# OutputConnectors.net
KiCad netlist of a schematic drawn in Altium Designer
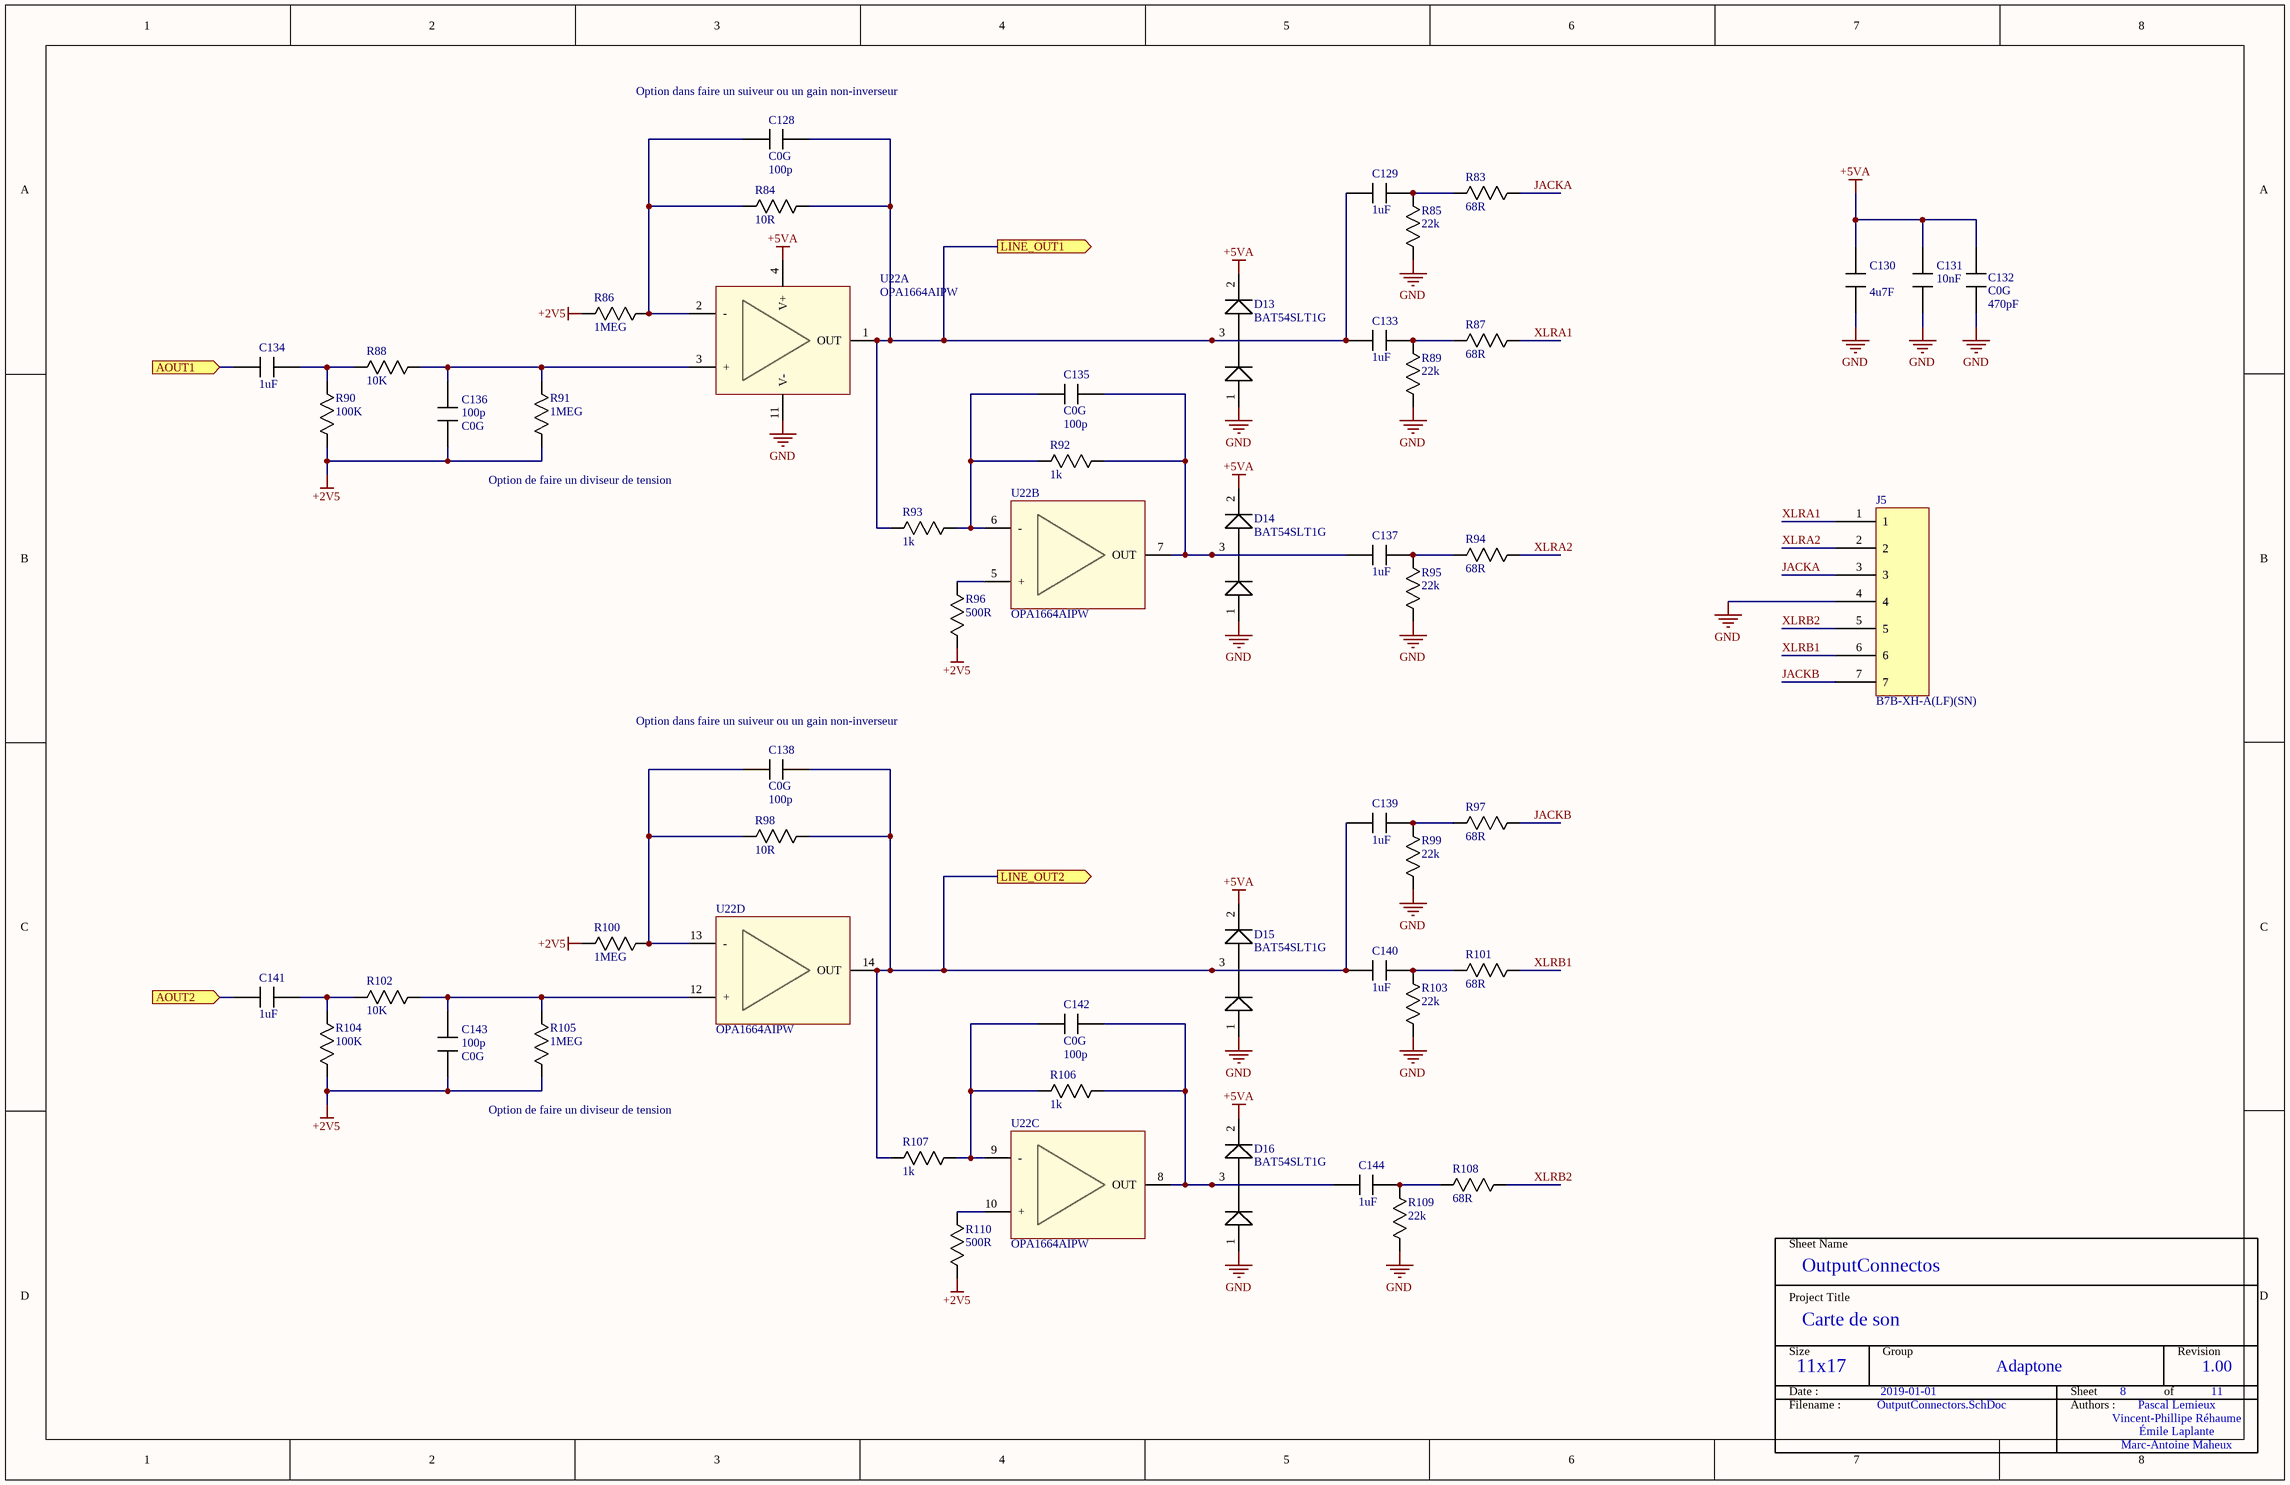
[diagram p0: OutputConnectors.SchDoc]

(export (version "E")
  (design (tool "Eeschema 10.0.6"))
  (components
    (comp (ref "C128")
      (value "100p")
      (footprint "0402")
      (description "Capacitor")
      (fields (field (name "MFG") "Yageo") (field (name "TYPE") "C0G"))
      (libsource (lib "LIB_ADAPTONE_PASCAL_LEMIEUX") (part "Capacitor"))
    )
    (comp (ref "C129")
      (value "1uF")
      (footprint "0402")
      (description "Capacitor")
      (fields (field (name "MFG") "Samsung Electro-Mechanics"))
      (libsource (lib "LIB_ADAPTONE_PASCAL_LEMIEUX") (part "Capacitor"))
    )
    (comp (ref "C130")
      (value "4u7F")
      (footprint "0805")
      (description "Capacitor")
      (fields (field (name "MFG") "Samsung"))
      (libsource (lib "ADAPTONE_CARTE_DE_SON") (part "Capacitor"))
    )
    (comp (ref "C131")
      (value "10nF")
      (footprint "0603")
      (description "Capacitor")
      (fields (field (name "MFG") "Murata"))
      (libsource (lib "ADAPTONE_CARTE_DE_SON") (part "Capacitor"))
    )
    (comp (ref "C132")
      (value "470pF")
      (footprint "0603")
      (description "Capacitor")
      (fields (field (name "MFG") "Samsung") (field (name "TYPE") "C0G"))
      (libsource (lib "ADAPTONE_CARTE_DE_SON") (part "Capacitor"))
    )
    (comp (ref "C133")
      (value "1uF")
      (footprint "0402")
      (description "Capacitor")
      (fields (field (name "MFG") "Samsung Electro-Mechanics"))
      (libsource (lib "LIB_ADAPTONE_PASCAL_LEMIEUX") (part "Capacitor"))
    )
    (comp (ref "C134")
      (value "1uF")
      (footprint "0402")
      (description "Capacitor")
      (fields (field (name "MFG") "Samsung Electro-Mechanics"))
      (libsource (lib "LIB_ADAPTONE_PASCAL_LEMIEUX") (part "Capacitor"))
    )
    (comp (ref "C135")
      (value "100p")
      (footprint "0402")
      (description "Capacitor")
      (fields (field (name "MFG") "Yageo") (field (name "TYPE") "C0G"))
      (libsource (lib "LIB_ADAPTONE_PASCAL_LEMIEUX") (part "Capacitor"))
    )
    (comp (ref "C136")
      (value "100p")
      (footprint "0402")
      (description "Capacitor")
      (fields (field (name "MFG") "Yageo") (field (name "TYPE") "C0G"))
      (libsource (lib "LIB_ADAPTONE_PASCAL_LEMIEUX") (part "Capacitor"))
    )
    (comp (ref "C137")
      (value "1uF")
      (footprint "0402")
      (description "Capacitor")
      (fields (field (name "MFG") "Samsung Electro-Mechanics"))
      (libsource (lib "LIB_ADAPTONE_PASCAL_LEMIEUX") (part "Capacitor"))
    )
    (comp (ref "C138")
      (value "100p")
      (footprint "0402")
      (description "Capacitor")
      (fields (field (name "MFG") "Yageo") (field (name "TYPE") "C0G"))
      (libsource (lib "LIB_ADAPTONE_PASCAL_LEMIEUX") (part "Capacitor"))
    )
    (comp (ref "C139")
      (value "1uF")
      (footprint "0402")
      (description "Capacitor")
      (fields (field (name "MFG") "Samsung Electro-Mechanics"))
      (libsource (lib "LIB_ADAPTONE_PASCAL_LEMIEUX") (part "Capacitor"))
    )
    (comp (ref "C140")
      (value "1uF")
      (footprint "0402")
      (description "Capacitor")
      (fields (field (name "MFG") "Samsung Electro-Mechanics"))
      (libsource (lib "LIB_ADAPTONE_PASCAL_LEMIEUX") (part "Capacitor"))
    )
    (comp (ref "C141")
      (value "1uF")
      (footprint "0402")
      (description "Capacitor")
      (fields (field (name "MFG") "Samsung Electro-Mechanics"))
      (libsource (lib "LIB_ADAPTONE_PASCAL_LEMIEUX") (part "Capacitor"))
    )
    (comp (ref "C142")
      (value "100p")
      (footprint "0402")
      (description "Capacitor")
      (fields (field (name "MFG") "Yageo") (field (name "TYPE") "C0G"))
      (libsource (lib "LIB_ADAPTONE_PASCAL_LEMIEUX") (part "Capacitor"))
    )
    (comp (ref "C143")
      (value "100p")
      (footprint "0402")
      (description "Capacitor")
      (fields (field (name "MFG") "Yageo") (field (name "TYPE") "C0G"))
      (libsource (lib "LIB_ADAPTONE_PASCAL_LEMIEUX") (part "Capacitor"))
    )
    (comp (ref "C144")
      (value "1uF")
      (footprint "0402")
      (description "Capacitor")
      (fields (field (name "MFG") "Samsung Electro-Mechanics"))
      (libsource (lib "LIB_ADAPTONE_PASCAL_LEMIEUX") (part "Capacitor"))
    )
    (comp (ref "D13")
      (value "Diode_dual")
      (footprint "SOT23_132")
      (description "Diode")
      (fields (field (name "MFG") "Onsemi") (field (name "MFG_PN") "BAT54SLT1G"))
      (libsource (lib "ADAPTONE_CARTE_DE_SON") (part "Diode_dual"))
    )
    (comp (ref "D14")
      (value "Diode_dual")
      (footprint "SOT23_132")
      (description "Diode")
      (fields (field (name "MFG") "Onsemi") (field (name "MFG_PN") "BAT54SLT1G"))
      (libsource (lib "ADAPTONE_CARTE_DE_SON") (part "Diode_dual"))
    )
    (comp (ref "D15")
      (value "Diode_dual")
      (footprint "SOT23_132")
      (description "Diode")
      (fields (field (name "MFG") "Onsemi") (field (name "MFG_PN") "BAT54SLT1G"))
      (libsource (lib "ADAPTONE_CARTE_DE_SON") (part "Diode_dual"))
    )
    (comp (ref "D16")
      (value "Diode_dual")
      (footprint "SOT23_132")
      (description "Diode")
      (fields (field (name "MFG") "Onsemi") (field (name "MFG_PN") "BAT54SLT1G"))
      (libsource (lib "ADAPTONE_CARTE_DE_SON") (part "Diode_dual"))
    )
    (comp (ref "J5")
      (value "B7B-XH-A(LF)(SN)")
      (footprint "CONN_7_HEADER")
      (fields (field (name "MFG") "JST Sales America Inc."))
      (libsource (lib "LIB_ADAPTONE_PASCAL_LEMIEUX") (part "CON_XH_JST_7pins"))
    )
    (comp (ref "R83")
      (value "68R")
      (footprint "0402")
      (description "Resistor")
      (fields (field (name "MFG") "Yageo"))
      (libsource (lib "LIB_ADAPTONE_PASCAL_LEMIEUX") (part "Resistor"))
    )
    (comp (ref "R84")
      (value "10R")
      (footprint "0402")
      (description "Resistor")
      (fields (field (name "MFG") "Yageo"))
      (libsource (lib "LIB_ADAPTONE_PASCAL_LEMIEUX") (part "Resistor"))
    )
    (comp (ref "R85")
      (value "22k")
      (footprint "0402")
      (description "Resistor")
      (fields (field (name "MFG") "Yageo"))
      (libsource (lib "LIB_ADAPTONE_PASCAL_LEMIEUX") (part "Resistor"))
    )
    (comp (ref "R86")
      (value "1MEG")
      (footprint "0402")
      (description "Resistor")
      (fields (field (name "MFG") "Yageo"))
      (libsource (lib "LIB_ADAPTONE_PASCAL_LEMIEUX") (part "Resistor"))
    )
    (comp (ref "R87")
      (value "68R")
      (footprint "0402")
      (description "Resistor")
      (fields (field (name "MFG") "Yageo"))
      (libsource (lib "LIB_ADAPTONE_PASCAL_LEMIEUX") (part "Resistor"))
    )
    (comp (ref "R88")
      (value "10K")
      (footprint "0402")
      (description "Resistor")
      (fields (field (name "MFG") "Yageo"))
      (libsource (lib "LIB_ADAPTONE_PASCAL_LEMIEUX") (part "Resistor"))
    )
    (comp (ref "R89")
      (value "22k")
      (footprint "0402")
      (description "Resistor")
      (fields (field (name "MFG") "Yageo"))
      (libsource (lib "LIB_ADAPTONE_PASCAL_LEMIEUX") (part "Resistor"))
    )
    (comp (ref "R90")
      (value "100K")
      (footprint "0402")
      (description "Resistor")
      (fields (field (name "MFG") "Yageo"))
      (libsource (lib "LIB_ADAPTONE_PASCAL_LEMIEUX") (part "Resistor"))
    )
    (comp (ref "R91")
      (value "1MEG")
      (footprint "0402")
      (description "Resistor")
      (fields (field (name "MFG") "Yageo"))
      (libsource (lib "LIB_ADAPTONE_PASCAL_LEMIEUX") (part "Resistor"))
    )
    (comp (ref "R92")
      (value "1k")
      (footprint "0402")
      (description "Resistor")
      (fields (field (name "MFG") "Yageo"))
      (libsource (lib "LIB_ADAPTONE_PASCAL_LEMIEUX") (part "Resistor"))
    )
    (comp (ref "R93")
      (value "1k")
      (footprint "0402")
      (description "Resistor")
      (fields (field (name "MFG") "Yageo"))
      (libsource (lib "LIB_ADAPTONE_PASCAL_LEMIEUX") (part "Resistor"))
    )
    (comp (ref "R94")
      (value "68R")
      (footprint "0402")
      (description "Resistor")
      (fields (field (name "MFG") "Yageo"))
      (libsource (lib "LIB_ADAPTONE_PASCAL_LEMIEUX") (part "Resistor"))
    )
    (comp (ref "R95")
      (value "22k")
      (footprint "0402")
      (description "Resistor")
      (fields (field (name "MFG") "Yageo"))
      (libsource (lib "LIB_ADAPTONE_PASCAL_LEMIEUX") (part "Resistor"))
    )
    (comp (ref "R96")
      (value "500R")
      (footprint "0402")
      (description "Resistor")
      (fields (field (name "MFG") "Yageo"))
      (libsource (lib "LIB_ADAPTONE_PASCAL_LEMIEUX") (part "Resistor"))
    )
    (comp (ref "R97")
      (value "68R")
      (footprint "0402")
      (description "Resistor")
      (fields (field (name "MFG") "Yageo"))
      (libsource (lib "LIB_ADAPTONE_PASCAL_LEMIEUX") (part "Resistor"))
    )
    (comp (ref "R98")
      (value "10R")
      (footprint "0402")
      (description "Resistor")
      (fields (field (name "MFG") "Yageo"))
      (libsource (lib "LIB_ADAPTONE_PASCAL_LEMIEUX") (part "Resistor"))
    )
    (comp (ref "R99")
      (value "22k")
      (footprint "0402")
      (description "Resistor")
      (fields (field (name "MFG") "Yageo"))
      (libsource (lib "LIB_ADAPTONE_PASCAL_LEMIEUX") (part "Resistor"))
    )
    (comp (ref "R100")
      (value "1MEG")
      (footprint "0402")
      (description "Resistor")
      (fields (field (name "MFG") "Yageo"))
      (libsource (lib "LIB_ADAPTONE_PASCAL_LEMIEUX") (part "Resistor"))
    )
    (comp (ref "R101")
      (value "68R")
      (footprint "0402")
      (description "Resistor")
      (fields (field (name "MFG") "Yageo"))
      (libsource (lib "LIB_ADAPTONE_PASCAL_LEMIEUX") (part "Resistor"))
    )
    (comp (ref "R102")
      (value "10K")
      (footprint "0402")
      (description "Resistor")
      (fields (field (name "MFG") "Yageo"))
      (libsource (lib "LIB_ADAPTONE_PASCAL_LEMIEUX") (part "Resistor"))
    )
    (comp (ref "R103")
      (value "22k")
      (footprint "0402")
      (description "Resistor")
      (fields (field (name "MFG") "Yageo"))
      (libsource (lib "LIB_ADAPTONE_PASCAL_LEMIEUX") (part "Resistor"))
    )
    (comp (ref "R104")
      (value "100K")
      (footprint "0402")
      (description "Resistor")
      (fields (field (name "MFG") "Yageo"))
      (libsource (lib "LIB_ADAPTONE_PASCAL_LEMIEUX") (part "Resistor"))
    )
    (comp (ref "R105")
      (value "1MEG")
      (footprint "0402")
      (description "Resistor")
      (fields (field (name "MFG") "Yageo"))
      (libsource (lib "LIB_ADAPTONE_PASCAL_LEMIEUX") (part "Resistor"))
    )
    (comp (ref "R106")
      (value "1k")
      (footprint "0402")
      (description "Resistor")
      (fields (field (name "MFG") "Yageo"))
      (libsource (lib "LIB_ADAPTONE_PASCAL_LEMIEUX") (part "Resistor"))
    )
    (comp (ref "R107")
      (value "1k")
      (footprint "0402")
      (description "Resistor")
      (fields (field (name "MFG") "Yageo"))
      (libsource (lib "LIB_ADAPTONE_PASCAL_LEMIEUX") (part "Resistor"))
    )
    (comp (ref "R108")
      (value "68R")
      (footprint "0402")
      (description "Resistor")
      (fields (field (name "MFG") "Yageo"))
      (libsource (lib "LIB_ADAPTONE_PASCAL_LEMIEUX") (part "Resistor"))
    )
    (comp (ref "R109")
      (value "22k")
      (footprint "0402")
      (description "Resistor")
      (fields (field (name "MFG") "Yageo"))
      (libsource (lib "LIB_ADAPTONE_PASCAL_LEMIEUX") (part "Resistor"))
    )
    (comp (ref "R110")
      (value "500R")
      (footprint "0402")
      (description "Resistor")
      (fields (field (name "MFG") "Yageo"))
      (libsource (lib "LIB_ADAPTONE_PASCAL_LEMIEUX") (part "Resistor"))
    )
    (comp (ref "U22")
      (value "OPA1664")
      (footprint "14-TSSOP")
      (description "Quad amplifier (audio)")
      (fields (field (name "MFG") "Texas Instruments") (field (name "MFG_PN") "OPA1664AIPW"))
      (libsource (lib "") (part "OPA1664_1"))
    )
  )
  (nets
    (net (code "1") (name "+2V5") (class "Default")
      (node (ref "C136") (pin "2") (pintype "passive"))
      (node (ref "C143") (pin "2") (pintype "passive"))
      (node (ref "R100") (pin "2") (pintype "passive"))
      (node (ref "R104") (pin "1") (pintype "passive"))
      (node (ref "R105") (pin "1") (pintype "passive"))
      (node (ref "R110") (pin "2") (pintype "passive"))
      (node (ref "R86") (pin "2") (pintype "passive"))
      (node (ref "R90") (pin "1") (pintype "passive"))
      (node (ref "R91") (pin "1") (pintype "passive"))
      (node (ref "R96") (pin "2") (pintype "passive"))
    )
    (net (code "2") (name "+5VA") (class "Default")
      (node (ref "C130") (pin "1") (pintype "passive"))
      (node (ref "C131") (pin "1") (pintype "passive"))
      (node (ref "C132") (pin "2") (pintype "passive"))
      (node (ref "D13") (pin "2") (pinfunction "K_2") (pintype "passive"))
      (node (ref "D14") (pin "2") (pinfunction "K_2") (pintype "passive"))
      (node (ref "D15") (pin "2") (pinfunction "K_2") (pintype "passive"))
      (node (ref "D16") (pin "2") (pinfunction "K_2") (pintype "passive"))
      (node (ref "U22") (pin "4") (pinfunction "V+_4") (pintype "passive"))
    )
    (net (code "3") (name "/AOUT1") (class "Default") (node (ref "C134") (pin "1") (pintype "passive")))
    (net (code "4") (name "/AOUT2") (class "Default") (node (ref "C141") (pin "1") (pintype "passive")))
    (net (code "5") (name "/JACKA") (class "Default")
      (node (ref "J5") (pin "3") (pinfunction "3_3") (pintype "passive"))
      (node (ref "R83") (pin "1") (pintype "passive"))
    )
    (net (code "6") (name "/JACKB") (class "Default")
      (node (ref "J5") (pin "7") (pinfunction "7_7") (pintype "passive"))
      (node (ref "R97") (pin "1") (pintype "passive"))
    )
    (net (code "7") (name "/LINE_OUT1") (class "Default")
      (node (ref "C128") (pin "2") (pintype "passive"))
      (node (ref "C129") (pin "1") (pintype "passive"))
      (node (ref "C133") (pin "1") (pintype "passive"))
      (node (ref "D13") (pin "3") (pinfunction "AK_3") (pintype "passive"))
      (node (ref "R84") (pin "1") (pintype "passive"))
      (node (ref "R93") (pin "2") (pintype "passive"))
      (node (ref "U22") (pin "1") (pinfunction "OUT_1") (pintype "passive"))
    )
    (net (code "8") (name "/LINE_OUT2") (class "Default")
      (node (ref "C138") (pin "2") (pintype "passive"))
      (node (ref "C139") (pin "1") (pintype "passive"))
      (node (ref "C140") (pin "1") (pintype "passive"))
      (node (ref "D15") (pin "3") (pinfunction "AK_3") (pintype "passive"))
      (node (ref "R107") (pin "2") (pintype "passive"))
      (node (ref "R98") (pin "1") (pintype "passive"))
      (node (ref "U22") (pin "14") (pinfunction "OUT_14") (pintype "passive"))
    )
    (net (code "9") (name "/XLRA1") (class "Default")
      (node (ref "J5") (pin "1") (pinfunction "1_1") (pintype "passive"))
      (node (ref "R87") (pin "1") (pintype "passive"))
    )
    (net (code "10") (name "/XLRA2") (class "Default")
      (node (ref "J5") (pin "2") (pinfunction "2_2") (pintype "passive"))
      (node (ref "R94") (pin "1") (pintype "passive"))
    )
    (net (code "11") (name "/XLRB1") (class "Default")
      (node (ref "J5") (pin "6") (pinfunction "6_6") (pintype "passive"))
      (node (ref "R101") (pin "1") (pintype "passive"))
    )
    (net (code "12") (name "/XLRB2") (class "Default")
      (node (ref "J5") (pin "5") (pinfunction "5_5") (pintype "passive"))
      (node (ref "R108") (pin "1") (pintype "passive"))
    )
    (net (code "13") (name "GND") (class "Default")
      (node (ref "C130") (pin "2") (pintype "passive"))
      (node (ref "C131") (pin "2") (pintype "passive"))
      (node (ref "C132") (pin "1") (pintype "passive"))
      (node (ref "D13") (pin "1") (pinfunction "K_1") (pintype "passive"))
      (node (ref "D14") (pin "1") (pinfunction "K_1") (pintype "passive"))
      (node (ref "D15") (pin "1") (pinfunction "K_1") (pintype "passive"))
      (node (ref "D16") (pin "1") (pinfunction "K_1") (pintype "passive"))
      (node (ref "J5") (pin "4") (pinfunction "4_4") (pintype "passive"))
      (node (ref "R103") (pin "1") (pintype "passive"))
      (node (ref "R109") (pin "1") (pintype "passive"))
      (node (ref "R85") (pin "1") (pintype "passive"))
      (node (ref "R89") (pin "1") (pintype "passive"))
      (node (ref "R95") (pin "1") (pintype "passive"))
      (node (ref "R99") (pin "1") (pintype "passive"))
      (node (ref "U22") (pin "11") (pinfunction "V-_11") (pintype "passive"))
    )
    (net (code "14") (name "Net-(C129-Pad2)") (class "Default")
      (node (ref "C129") (pin "2") (pintype "passive"))
      (node (ref "R83") (pin "2") (pintype "passive"))
      (node (ref "R85") (pin "2") (pintype "passive"))
    )
    (net (code "15") (name "Net-(C133-Pad2)") (class "Default")
      (node (ref "C133") (pin "2") (pintype "passive"))
      (node (ref "R87") (pin "2") (pintype "passive"))
      (node (ref "R89") (pin "2") (pintype "passive"))
    )
    (net (code "16") (name "Net-(C134-Pad2)") (class "Default")
      (node (ref "C134") (pin "2") (pintype "passive"))
      (node (ref "R88") (pin "1") (pintype "passive"))
      (node (ref "R90") (pin "2") (pintype "passive"))
    )
    (net (code "17") (name "Net-(C137-Pad2)") (class "Default")
      (node (ref "C137") (pin "2") (pintype "passive"))
      (node (ref "R94") (pin "2") (pintype "passive"))
      (node (ref "R95") (pin "2") (pintype "passive"))
    )
    (net (code "18") (name "Net-(C139-Pad2)") (class "Default")
      (node (ref "C139") (pin "2") (pintype "passive"))
      (node (ref "R97") (pin "2") (pintype "passive"))
      (node (ref "R99") (pin "2") (pintype "passive"))
    )
    (net (code "19") (name "Net-(C140-Pad2)") (class "Default")
      (node (ref "C140") (pin "2") (pintype "passive"))
      (node (ref "R101") (pin "2") (pintype "passive"))
      (node (ref "R103") (pin "2") (pintype "passive"))
    )
    (net (code "20") (name "Net-(C141-Pad2)") (class "Default")
      (node (ref "C141") (pin "2") (pintype "passive"))
      (node (ref "R102") (pin "1") (pintype "passive"))
      (node (ref "R104") (pin "2") (pintype "passive"))
    )
    (net (code "21") (name "Net-(C144-Pad2)") (class "Default")
      (node (ref "C144") (pin "2") (pintype "passive"))
      (node (ref "R108") (pin "2") (pintype "passive"))
      (node (ref "R109") (pin "2") (pintype "passive"))
    )
    (net (code "22") (name "Net-(D14-AK)") (class "Default")
      (node (ref "C135") (pin "2") (pintype "passive"))
      (node (ref "C137") (pin "1") (pintype "passive"))
      (node (ref "D14") (pin "3") (pinfunction "AK_3") (pintype "passive"))
      (node (ref "R92") (pin "1") (pintype "passive"))
      (node (ref "U22") (pin "7") (pinfunction "OUT_7") (pintype "passive"))
    )
    (net (code "23") (name "Net-(D16-AK)") (class "Default")
      (node (ref "C142") (pin "2") (pintype "passive"))
      (node (ref "C144") (pin "1") (pintype "passive"))
      (node (ref "D16") (pin "3") (pinfunction "AK_3") (pintype "passive"))
      (node (ref "R106") (pin "1") (pintype "passive"))
      (node (ref "U22") (pin "8") (pinfunction "OUT_8") (pintype "passive"))
    )
    (net (code "24") (name "Net-(U22A-+)") (class "Default")
      (node (ref "C136") (pin "1") (pintype "passive"))
      (node (ref "R88") (pin "2") (pintype "passive"))
      (node (ref "R91") (pin "2") (pintype "passive"))
      (node (ref "U22") (pin "3") (pinfunction "+_3") (pintype "passive"))
    )
    (net (code "25") (name "Net-(U22A--)") (class "Default")
      (node (ref "C128") (pin "1") (pintype "passive"))
      (node (ref "R84") (pin "2") (pintype "passive"))
      (node (ref "R86") (pin "1") (pintype "passive"))
      (node (ref "U22") (pin "2") (pinfunction "-_2") (pintype "passive"))
    )
    (net (code "26") (name "Net-(U22B-+)") (class "Default")
      (node (ref "R96") (pin "1") (pintype "passive"))
      (node (ref "U22") (pin "5") (pinfunction "+_5") (pintype "passive"))
    )
    (net (code "27") (name "Net-(U22B--)") (class "Default")
      (node (ref "C135") (pin "1") (pintype "passive"))
      (node (ref "R92") (pin "2") (pintype "passive"))
      (node (ref "R93") (pin "1") (pintype "passive"))
      (node (ref "U22") (pin "6") (pinfunction "-_6") (pintype "passive"))
    )
    (net (code "28") (name "Net-(U22C-+)") (class "Default")
      (node (ref "R110") (pin "1") (pintype "passive"))
      (node (ref "U22") (pin "10") (pinfunction "+_10") (pintype "passive"))
    )
    (net (code "29") (name "Net-(U22C--)") (class "Default")
      (node (ref "C142") (pin "1") (pintype "passive"))
      (node (ref "R106") (pin "2") (pintype "passive"))
      (node (ref "R107") (pin "1") (pintype "passive"))
      (node (ref "U22") (pin "9") (pinfunction "-_9") (pintype "passive"))
    )
    (net (code "30") (name "Net-(U22D-+)") (class "Default")
      (node (ref "C143") (pin "1") (pintype "passive"))
      (node (ref "R102") (pin "2") (pintype "passive"))
      (node (ref "R105") (pin "2") (pintype "passive"))
      (node (ref "U22") (pin "12") (pinfunction "+_12") (pintype "passive"))
    )
    (net (code "31") (name "Net-(U22D--)") (class "Default")
      (node (ref "C138") (pin "1") (pintype "passive"))
      (node (ref "R100") (pin "1") (pintype "passive"))
      (node (ref "R98") (pin "2") (pintype "passive"))
      (node (ref "U22") (pin "13") (pinfunction "-_13") (pintype "passive"))
    )
  )
)
